# 20190105_ORIGAMI_V1-H-08slot.net
KiCad netlist of a schematic drawn in EAGLE
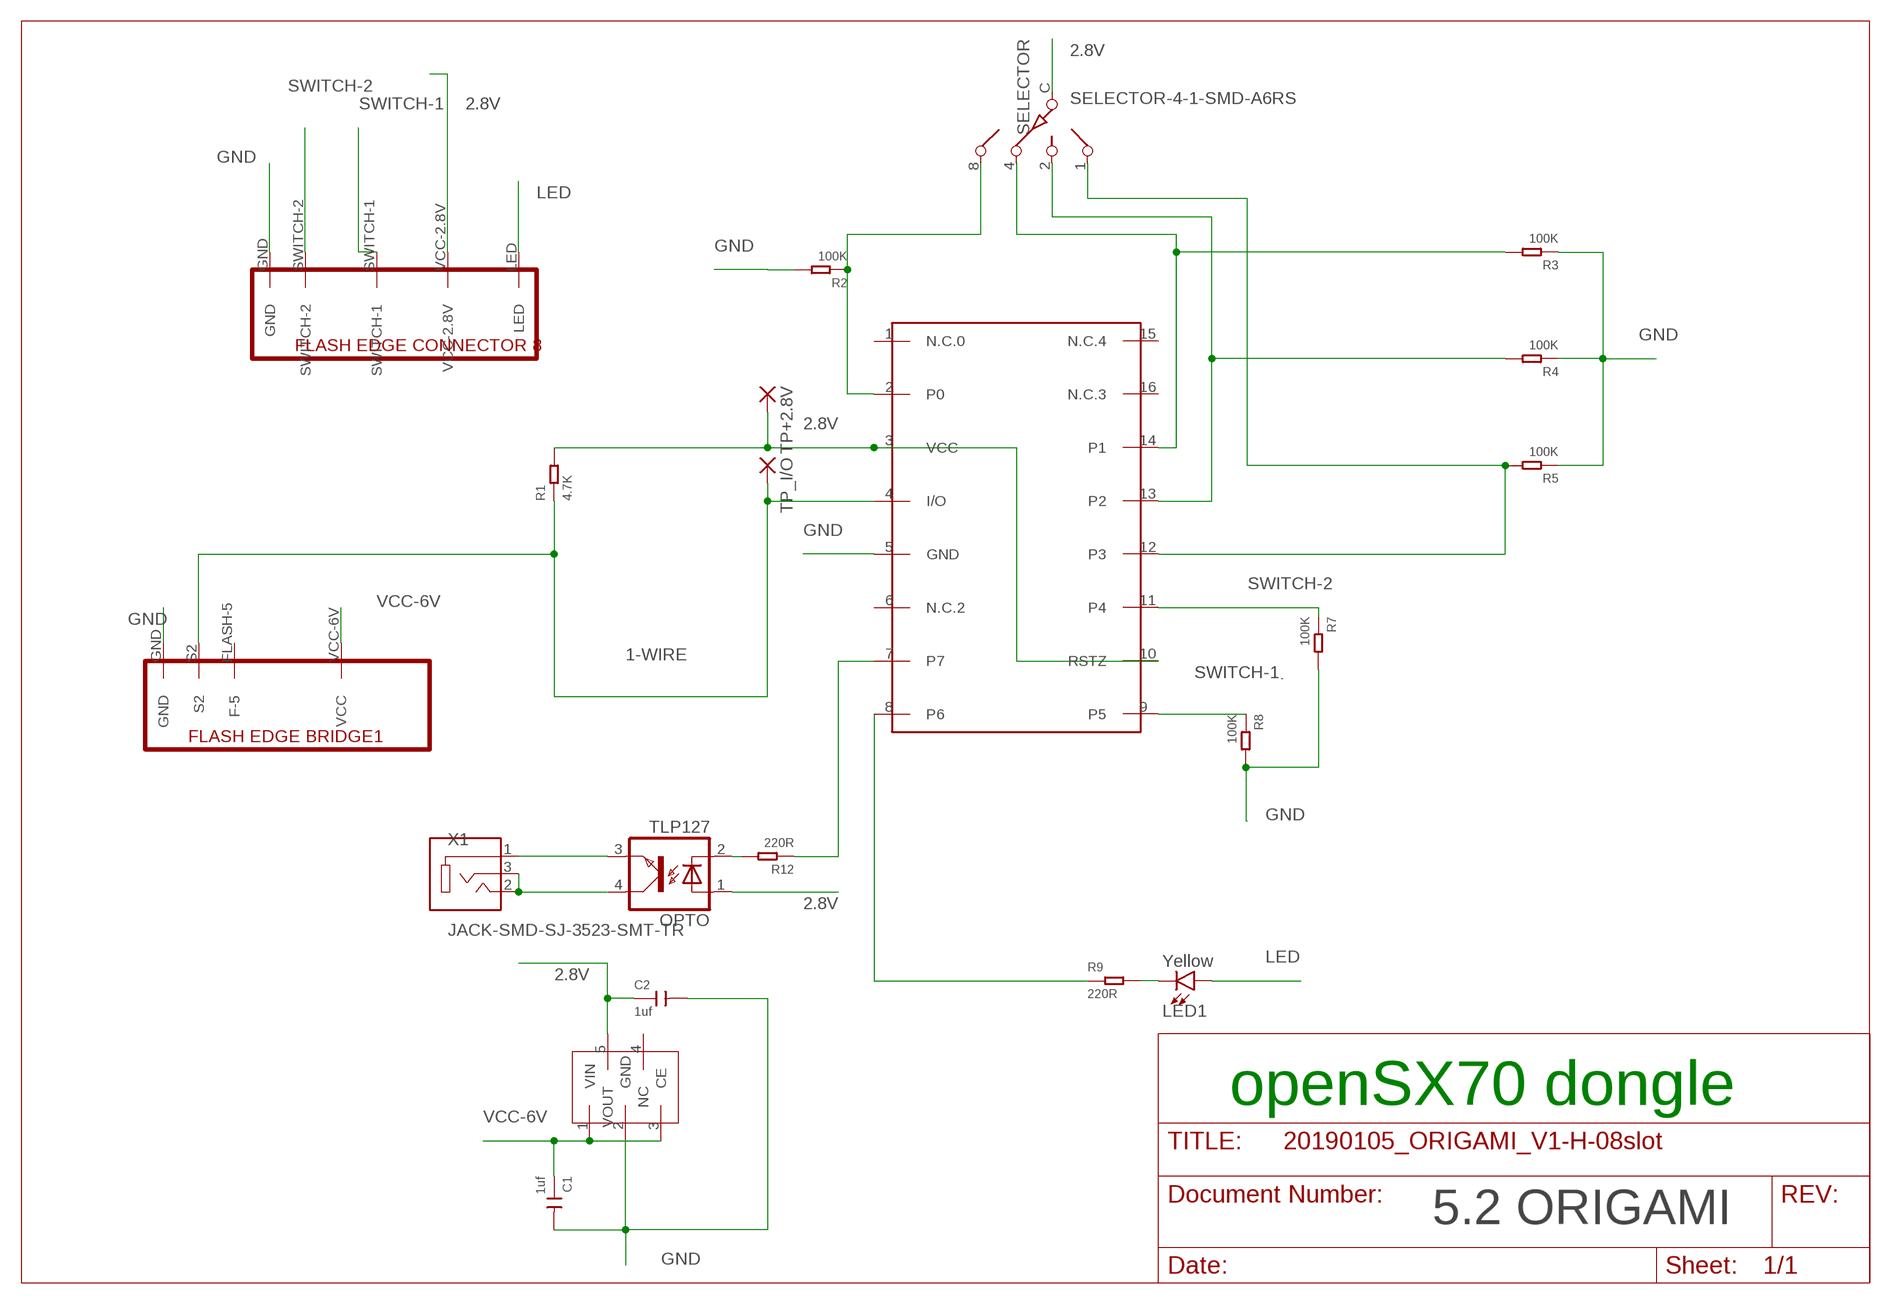
[diagram p0: schematic, sheet 1]

(export (version "E")
  (design (tool "Eeschema 10.0.6"))
  (components
    (comp (ref "C1")
      (value "1uf")
      (footprint "eagle-import:C0603")
      (fields (field (name "MPN") "CC0603KRX7R8BB105"))
      (libsource (lib "eagle-import") (part "CERAMIC-1UF-25V-10%-X7R(0603)"))
    )
    (comp (ref "C2")
      (value "1uf")
      (footprint "eagle-import:C0603")
      (fields (field (name "MPN") "CC0603KRX7R8BB105"))
      (libsource (lib "eagle-import") (part "CERAMIC-1UF-25V-10%-X7R(0603)"))
    )
    (comp (ref "DS2408")
      (value "DS2408")
      (footprint "eagle-import:SO16")
      (libsource (lib "eagle-import") (part "DS2408"))
    )
    (comp (ref "LED1")
      (value "Yellow")
      (footprint "eagle-import:LED-1206")
      (libsource (lib "eagle-import") (part "LED-YELLOWLILYPAD"))
    )
    (comp (ref "OPTO")
      (value "TLP127")
      (footprint "eagle-import:SO-4")
      (libsource (lib "eagle-import") (part "TLP127"))
    )
    (comp (ref "R1")
      (value "4.7K")
      (footprint "eagle-import:R0603")
      (fields (field (name "MPN") "RC0603JR-074K7L"))
      (libsource (lib "eagle-import") (part "SMD-RES-4.7K-5%-1/10W(0603)"))
    )
    (comp (ref "R2")
      (value "100K")
      (footprint "eagle-import:R0603")
      (fields (field (name "MPN") "RC0603FR-07100KL"))
      (libsource (lib "eagle-import") (part "SMD-RES-100K-1%-1/10W(0603)"))
    )
    (comp (ref "R3")
      (value "100K")
      (footprint "eagle-import:R0603")
      (fields (field (name "MPN") "RC0603FR-07100KL"))
      (libsource (lib "eagle-import") (part "SMD-RES-100K-1%-1/10W(0603)"))
    )
    (comp (ref "R4")
      (value "100K")
      (footprint "eagle-import:R0603")
      (fields (field (name "MPN") "RC0603FR-07100KL"))
      (libsource (lib "eagle-import") (part "SMD-RES-100K-1%-1/10W(0603)"))
    )
    (comp (ref "R5")
      (value "100K")
      (footprint "eagle-import:R0603")
      (fields (field (name "MPN") "RC0603FR-07100KL"))
      (libsource (lib "eagle-import") (part "SMD-RES-100K-1%-1/10W(0603)"))
    )
    (comp (ref "R7")
      (value "100K")
      (footprint "eagle-import:R0603")
      (fields (field (name "MPN") "RC0603FR-07100KL"))
      (libsource (lib "eagle-import") (part "SMD-RES-100K-1%-1/10W(0603)"))
    )
    (comp (ref "R8")
      (value "100K")
      (footprint "eagle-import:R0603")
      (fields (field (name "MPN") "RC0603FR-07100KL"))
      (libsource (lib "eagle-import") (part "SMD-RES-100K-1%-1/10W(0603)"))
    )
    (comp (ref "R9")
      (value "220R")
      (footprint "eagle-import:R0603")
      (fields (field (name "MPN") "RC0603JR-07220RL"))
      (libsource (lib "eagle-import") (part "SMD-RES-220R-5%-1/10W(0603)"))
    )
    (comp (ref "R12")
      (value "220R")
      (footprint "eagle-import:R0603")
      (fields (field (name "MPN") "RC0603JR-07220RL"))
      (libsource (lib "eagle-import") (part "SMD-RES-220R-5%-1/10W(0603)"))
    )
    (comp (ref "REG")
      (value "NCP4688")
      (footprint "eagle-import:SOT-23-5")
      (libsource (lib "eagle-import") (part "NCP4688"))
    )
    (comp (ref "SELECTOR")
      (value "SELECTOR-4-1-SMD-A6RS")
      (footprint "eagle-import:A6RS-161RS")
      (libsource (lib "eagle-import") (part "SELECTOR-4-1-SMD-A6RS"))
    )
    (comp (ref "TP+2.8V")
      (value "SMD2")
      (footprint "eagle-import:SMD1,27-2,54")
      (libsource (lib "eagle-import") (part "SMD2"))
    )
    (comp (ref "TP_I/O")
      (value "SMD2")
      (footprint "eagle-import:SMD1,27-2,54")
      (libsource (lib "eagle-import") (part "SMD2"))
    )
    (comp (ref "U$1")
      (value "FLASH-BRIDGE-SW1-SW2-LED")
      (footprint "eagle-import:FLASH-8-BRIDGE-SW1-SW2-LED")
      (libsource (lib "eagle-import") (part "FLASH-BRIDGE-SW1-SW2-LED"))
    )
    (comp (ref "U$2")
      (value "FLASH-BRIDGE1")
      (footprint "eagle-import:FLASH-8-BRIDGE1")
      (libsource (lib "eagle-import") (part "FLASH-BRIDGE1"))
    )
    (comp (ref "X1")
      (value "JACK-SMD-SJ-3523-SMT-TR")
      (footprint "eagle-import:CUI_SJ-3523-SMT-TR")
      (fields (field (name "MF") "CUI Inc.") (field (name "MP") "SJ-3523-SMT-TR"))
      (libsource (lib "eagle-import") (part "JACK-SMD-SJ-3523-SMT-TR"))
    )
  )
  (nets
    (net (code "1") (name "/1-WIRE") (class "Default")
      (node (ref "DS2408") (pin "4") (pinfunction "I/O_4") (pintype "bidirectional"))
      (node (ref "R1") (pin "1") (pinfunction "1_1") (pintype "passive"))
      (node (ref "TP_I/O") (pin "1") (pinfunction "P_1") (pintype "passive"))
      (node (ref "U$2") (pin "S2") (pinfunction "S2_S2") (pintype "bidirectional"))
    )
    (net (code "2") (name "/2.8V") (class "Default")
      (node (ref "C2") (pin "1") (pinfunction "1_1") (pintype "passive"))
      (node (ref "DS2408") (pin "10") (pinfunction "RSTZ_10") (pintype "bidirectional"))
      (node (ref "DS2408") (pin "3") (pinfunction "VCC_3") (pintype "bidirectional"))
      (node (ref "OPTO") (pin "1") (pinfunction "A_1") (pintype "passive"))
      (node (ref "R1") (pin "2") (pinfunction "2_2") (pintype "passive"))
      (node (ref "REG") (pin "5") (pinfunction "VOUT_5") (pintype "bidirectional"))
      (node (ref "SELECTOR") (pin "C") (pinfunction "C_C") (pintype "passive"))
      (node (ref "TP+2.8V") (pin "1") (pinfunction "P_1") (pintype "passive"))
      (node (ref "U$1") (pin "VCC-2.8V") (pinfunction "VCC-2.8V_VCC-2.8V") (pintype "bidirectional"))
    )
    (net (code "3") (name "/GND") (class "Default")
      (node (ref "C1") (pin "2") (pinfunction "2_2") (pintype "passive"))
      (node (ref "C2") (pin "2") (pinfunction "2_2") (pintype "passive"))
      (node (ref "DS2408") (pin "5") (pinfunction "GND_5") (pintype "bidirectional"))
      (node (ref "R2") (pin "2") (pinfunction "2_2") (pintype "passive"))
      (node (ref "R3") (pin "1") (pinfunction "1_1") (pintype "passive"))
      (node (ref "R4") (pin "1") (pinfunction "1_1") (pintype "passive"))
      (node (ref "R5") (pin "1") (pinfunction "1_1") (pintype "passive"))
      (node (ref "R7") (pin "2") (pinfunction "2_2") (pintype "passive"))
      (node (ref "R8") (pin "2") (pinfunction "2_2") (pintype "passive"))
      (node (ref "REG") (pin "2") (pinfunction "GND_2") (pintype "bidirectional"))
      (node (ref "U$1") (pin "GND") (pinfunction "GND_GND") (pintype "bidirectional"))
      (node (ref "U$2") (pin "GND") (pinfunction "GND_GND") (pintype "bidirectional"))
    )
    (net (code "4") (name "/LED") (class "Default")
      (node (ref "LED1") (pin "A") (pinfunction "A_A") (pintype "passive"))
      (node (ref "U$1") (pin "LED") (pinfunction "LED_LED") (pintype "bidirectional"))
    )
    (net (code "5") (name "/SWITCH-1") (class "Default")
      (node (ref "DS2408") (pin "9") (pinfunction "P5_9") (pintype "bidirectional"))
      (node (ref "R8") (pin "1") (pinfunction "1_1") (pintype "passive"))
      (node (ref "U$1") (pin "SWITCH-1") (pinfunction "SWITCH-1_SWITCH-1") (pintype "bidirectional"))
    )
    (net (code "6") (name "/SWITCH-2") (class "Default")
      (node (ref "DS2408") (pin "11") (pinfunction "P4_11") (pintype "bidirectional"))
      (node (ref "R7") (pin "1") (pinfunction "1_1") (pintype "passive"))
      (node (ref "U$1") (pin "SWITCH-2") (pinfunction "SWITCH-2_SWITCH-2") (pintype "bidirectional"))
    )
    (net (code "7") (name "/VCC-6V") (class "Default")
      (node (ref "C1") (pin "1") (pinfunction "1_1") (pintype "passive"))
      (node (ref "REG") (pin "1") (pinfunction "VIN_1") (pintype "bidirectional"))
      (node (ref "REG") (pin "3") (pinfunction "CE_3") (pintype "bidirectional"))
      (node (ref "U$2") (pin "VCC-6V") (pinfunction "VCC_VCC-6V") (pintype "bidirectional"))
    )
    (net (code "8") (name "Net-(DS2408-P0)") (class "Default")
      (node (ref "DS2408") (pin "2") (pinfunction "P0_2") (pintype "bidirectional"))
      (node (ref "R2") (pin "1") (pinfunction "1_1") (pintype "passive"))
      (node (ref "SELECTOR") (pin "8") (pinfunction "8_8") (pintype "passive"))
    )
    (net (code "9") (name "Net-(DS2408-P1)") (class "Default")
      (node (ref "DS2408") (pin "14") (pinfunction "P1_14") (pintype "bidirectional"))
      (node (ref "R3") (pin "2") (pinfunction "2_2") (pintype "passive"))
      (node (ref "SELECTOR") (pin "4") (pinfunction "4_4") (pintype "passive"))
    )
    (net (code "10") (name "Net-(DS2408-P2)") (class "Default")
      (node (ref "DS2408") (pin "13") (pinfunction "P2_13") (pintype "bidirectional"))
      (node (ref "R4") (pin "2") (pinfunction "2_2") (pintype "passive"))
      (node (ref "SELECTOR") (pin "2") (pinfunction "2_2") (pintype "passive"))
    )
    (net (code "11") (name "Net-(DS2408-P3)") (class "Default")
      (node (ref "DS2408") (pin "12") (pinfunction "P3_12") (pintype "bidirectional"))
      (node (ref "R5") (pin "2") (pinfunction "2_2") (pintype "passive"))
      (node (ref "SELECTOR") (pin "1") (pinfunction "1_1") (pintype "passive"))
    )
    (net (code "12") (name "Net-(DS2408-P6)") (class "Default")
      (node (ref "DS2408") (pin "8") (pinfunction "P6_8") (pintype "bidirectional"))
      (node (ref "R9") (pin "1") (pinfunction "1_1") (pintype "passive"))
    )
    (net (code "13") (name "Net-(DS2408-P7)") (class "Default")
      (node (ref "DS2408") (pin "7") (pinfunction "P7_7") (pintype "bidirectional"))
      (node (ref "R12") (pin "1") (pinfunction "1_1") (pintype "passive"))
    )
    (net (code "14") (name "Net-(LED1-PadC)") (class "Default")
      (node (ref "LED1") (pin "C") (pinfunction "C_C") (pintype "passive"))
      (node (ref "R9") (pin "2") (pinfunction "2_2") (pintype "passive"))
    )
    (net (code "15") (name "Net-(OPTO-C)") (class "Default")
      (node (ref "OPTO") (pin "2") (pinfunction "C_2") (pintype "passive"))
      (node (ref "R12") (pin "2") (pinfunction "2_2") (pintype "passive"))
    )
    (net (code "16") (name "Net-(OPTO-COL)") (class "Default")
      (node (ref "OPTO") (pin "4") (pinfunction "COL_4") (pintype "passive"))
      (node (ref "X1") (pin "2") (pinfunction "2_2") (pintype "passive"))
      (node (ref "X1") (pin "3") (pinfunction "3_3") (pintype "passive"))
    )
    (net (code "17") (name "Net-(OPTO-EMIT)") (class "Default")
      (node (ref "OPTO") (pin "3") (pinfunction "EMIT_3") (pintype "passive"))
      (node (ref "X1") (pin "1") (pinfunction "1_1") (pintype "passive"))
    )
    (net (code "18") (name "unconnected-(DS2408-N.C.0-Pad1)") (class "Default")
      (node (ref "DS2408") (pin "1") (pinfunction "N.C.0_1") (pintype "bidirectional"))
    )
    (net (code "19") (name "unconnected-(DS2408-N.C.2-Pad6)") (class "Default")
      (node (ref "DS2408") (pin "6") (pinfunction "N.C.2_6") (pintype "bidirectional"))
    )
    (net (code "20") (name "unconnected-(DS2408-N.C.3-Pad16)") (class "Default")
      (node (ref "DS2408") (pin "16") (pinfunction "N.C.3_16") (pintype "bidirectional"))
    )
    (net (code "21") (name "unconnected-(DS2408-N.C.4-Pad15)") (class "Default")
      (node (ref "DS2408") (pin "15") (pinfunction "N.C.4_15") (pintype "bidirectional"))
    )
    (net (code "22") (name "unconnected-(REG-NC-Pad4)") (class "Default")
      (node (ref "REG") (pin "4") (pinfunction "NC_4") (pintype "bidirectional"))
    )
    (net (code "23") (name "unconnected-(U$2-F-5-PadFLASH-5)") (class "Default")
      (node (ref "U$2") (pin "FLASH-5") (pinfunction "F-5_FLASH-5") (pintype "bidirectional"))
    )
  )
)
